# barometer.net
KiCad netlist of a schematic drawn in EAGLE
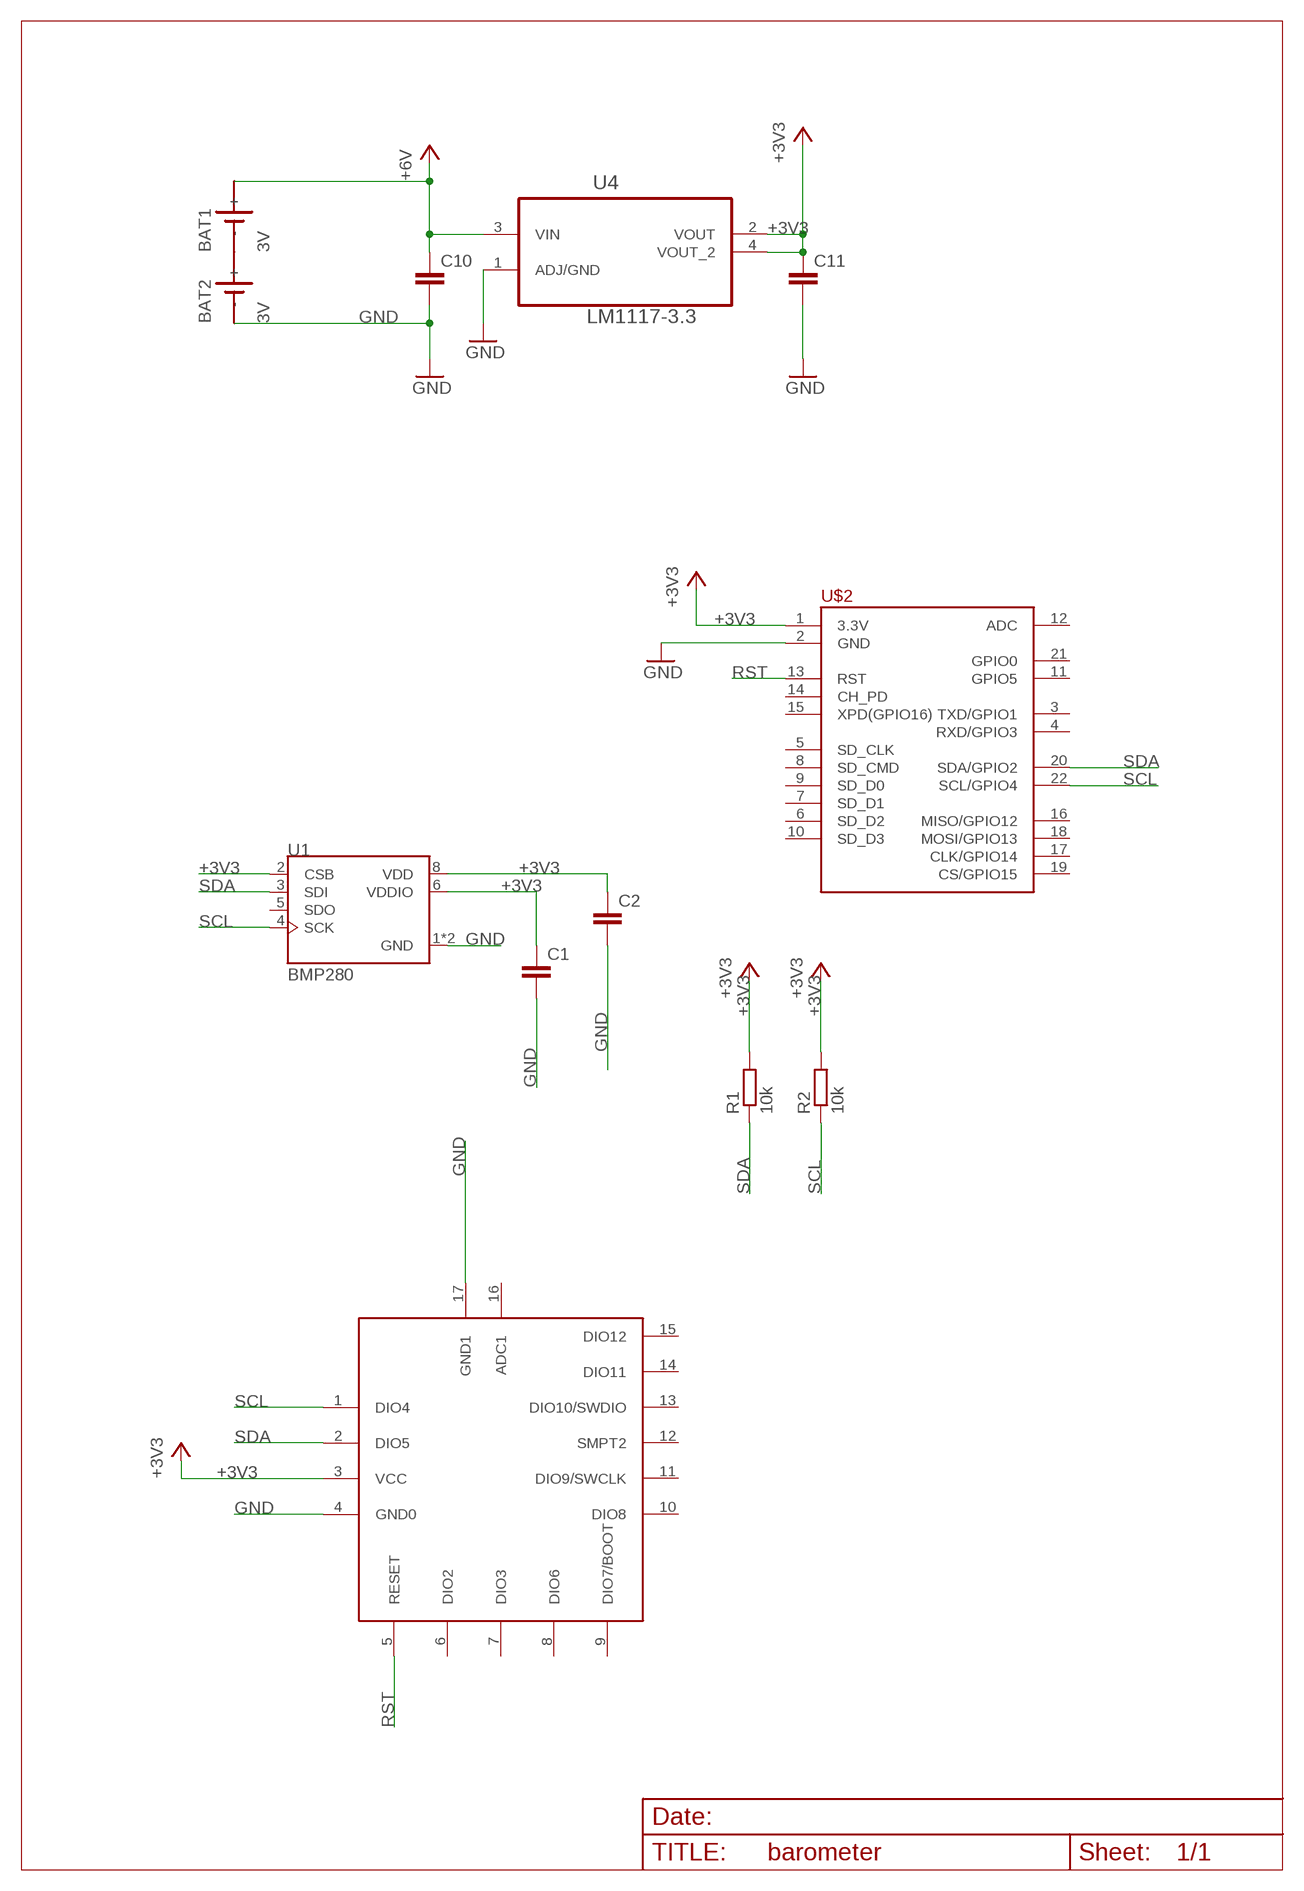
[diagram p0: schematic, sheet 1]

(export (version "E")
  (design (tool "Eeschema 10.0.6"))
  (components
    (comp (ref "BAT1")
      (value "3V")
      (footprint "eagle-import:SN2032")
      (libsource (lib "eagle-import") (part "SN2032"))
    )
    (comp (ref "BAT2")
      (value "3V")
      (footprint "eagle-import:SN2032")
      (libsource (lib "eagle-import") (part "SN2032"))
    )
    (comp (ref "C1")
      (value "47u")
      (footprint "eagle-import:C1206")
      (libsource (lib "eagle-import") (part "C-EUC1206"))
    )
    (comp (ref "C2")
      (value "47u")
      (footprint "eagle-import:C1206")
      (libsource (lib "eagle-import") (part "C-EUC1206"))
    )
    (comp (ref "C10")
      (value "47u")
      (footprint "eagle-import:C1206")
      (libsource (lib "eagle-import") (part "C-EUC1206"))
    )
    (comp (ref "C11")
      (value "10u")
      (footprint "eagle-import:C1206")
      (libsource (lib "eagle-import") (part "C-EUC1206"))
    )
    (comp (ref "R1")
      (value "10k")
      (footprint "eagle-import:R0402")
      (libsource (lib "eagle-import") (part "R-EU_R0402"))
    )
    (comp (ref "R2")
      (value "10k")
      (footprint "eagle-import:R0402")
      (libsource (lib "eagle-import") (part "R-EU_R0402"))
    )
    (comp (ref "U$1")
      (value "BLUENRG-234BLEMODULE")
      (footprint "eagle-import:BLUENRG-234BLEMODULE")
      (libsource (lib "eagle-import") (part "BLUENRG-234BLEMODULE"))
    )
    (comp (ref "U$2")
      (value "OLIMEX_MOD-WIFI-ESP8266-DEV>PINS-OUTSIDE")
      (footprint "eagle-import:OLIMEX_MOD-WIFI-ESP8266-DEV-PINS-OUTSIDE")
      (libsource (lib "eagle-import") (part "OLIMEX_MOD-WIFI-ESP8266-DEV{gt}PINS-OUTSIDE"))
    )
    (comp (ref "U1")
      (value "BMP280")
      (footprint "eagle-import:XDCR_BMP280")
      (fields (field (name "MF") "Bosch"))
      (libsource (lib "eagle-import") (part "BMP280"))
    )
    (comp (ref "U4")
      (value "LM1117-3.3")
      (footprint "eagle-import:SOT230")
      (fields (field (name "MF") "Texas Instruments"))
      (libsource (lib "eagle-import") (part "LM1117-3.3"))
    )
  )
  (nets
    (net (code "1") (name "+3V3") (class "Default")
      (node (ref "C1") (pin "1") (pinfunction "1_1") (pintype "passive"))
      (node (ref "C11") (pin "1") (pinfunction "1_1") (pintype "passive"))
      (node (ref "C2") (pin "1") (pinfunction "1_1") (pintype "passive"))
      (node (ref "R1") (pin "2") (pinfunction "2_2") (pintype "passive"))
      (node (ref "R2") (pin "2") (pinfunction "2_2") (pintype "passive"))
      (node (ref "U$1") (pin "3") (pinfunction "VCC_3") (pintype "bidirectional"))
      (node (ref "U$2") (pin "1") (pinfunction "3.3V_1") (pintype "power_in"))
      (node (ref "U1") (pin "2") (pinfunction "CSB_2") (pintype "input"))
      (node (ref "U1") (pin "6") (pinfunction "VDDIO_6") (pintype "power_in"))
      (node (ref "U1") (pin "8") (pinfunction "VDD_8") (pintype "power_in"))
      (node (ref "U4") (pin "2") (pinfunction "VOUT_2") (pintype "output"))
      (node (ref "U4") (pin "4") (pinfunction "VOUT_2_4") (pintype "output"))
    )
    (net (code "2") (name "+6V") (class "Default")
      (node (ref "BAT1") (pin "+") (pinfunction "+_+") (pintype "passive"))
      (node (ref "C10") (pin "1") (pinfunction "1_1") (pintype "passive"))
      (node (ref "U4") (pin "3") (pinfunction "VIN_3") (pintype "input"))
    )
    (net (code "3") (name "/RST") (class "Default")
      (node (ref "U$1") (pin "5") (pinfunction "RESET_5") (pintype "bidirectional"))
      (node (ref "U$2") (pin "13") (pinfunction "RST_13") (pintype "input"))
    )
    (net (code "4") (name "/SCL") (class "Default")
      (node (ref "R2") (pin "1") (pinfunction "1_1") (pintype "passive"))
      (node (ref "U$1") (pin "1") (pinfunction "DIO4_1") (pintype "bidirectional"))
      (node (ref "U$2") (pin "22") (pinfunction "SCL/GPIO4_22") (pintype "bidirectional"))
      (node (ref "U1") (pin "4") (pinfunction "SCK_4") (pintype "input"))
    )
    (net (code "5") (name "/SDA") (class "Default")
      (node (ref "R1") (pin "1") (pinfunction "1_1") (pintype "passive"))
      (node (ref "U$1") (pin "2") (pinfunction "DIO5_2") (pintype "bidirectional"))
      (node (ref "U$2") (pin "20") (pinfunction "SDA/GPIO2_20") (pintype "bidirectional"))
      (node (ref "U1") (pin "3") (pinfunction "SDI_3") (pintype "bidirectional"))
    )
    (net (code "6") (name "GND") (class "Default")
      (node (ref "BAT2") (pin "-") (pinfunction "-_-") (pintype "passive"))
      (node (ref "C1") (pin "2") (pinfunction "2_2") (pintype "passive"))
      (node (ref "C10") (pin "2") (pinfunction "2_2") (pintype "passive"))
      (node (ref "C11") (pin "2") (pinfunction "2_2") (pintype "passive"))
      (node (ref "C2") (pin "2") (pinfunction "2_2") (pintype "passive"))
      (node (ref "U$1") (pin "17") (pinfunction "GND1_17") (pintype "bidirectional"))
      (node (ref "U$1") (pin "4") (pinfunction "GND0_4") (pintype "bidirectional"))
      (node (ref "U$2") (pin "2") (pinfunction "GND_2") (pintype "power_in"))
      (node (ref "U1") (pin "1") (pinfunction "GND_1") (pintype "power_in"))
      (node (ref "U1") (pin "7") (pinfunction "GND_7") (pintype "power_in"))
      (node (ref "U4") (pin "1") (pinfunction "ADJ/GND_1") (pintype "passive"))
    )
    (net (code "7") (name "Net-(BAT1-Pad-)") (class "Default")
      (node (ref "BAT1") (pin "-") (pinfunction "-_-") (pintype "passive"))
      (node (ref "BAT2") (pin "+") (pinfunction "+_+") (pintype "passive"))
    )
    (net (code "8") (name "unconnected-(U$1-ADC1-Pad16)") (class "Default")
      (node (ref "U$1") (pin "16") (pinfunction "ADC1_16") (pintype "bidirectional"))
    )
    (net (code "9") (name "unconnected-(U$1-DIO2-Pad6)") (class "Default")
      (node (ref "U$1") (pin "6") (pinfunction "DIO2_6") (pintype "bidirectional"))
    )
    (net (code "10") (name "unconnected-(U$1-DIO3-Pad7)") (class "Default")
      (node (ref "U$1") (pin "7") (pinfunction "DIO3_7") (pintype "bidirectional"))
    )
    (net (code "11") (name "unconnected-(U$1-DIO6-Pad8)") (class "Default")
      (node (ref "U$1") (pin "8") (pinfunction "DIO6_8") (pintype "bidirectional"))
    )
    (net (code "12") (name "unconnected-(U$1-DIO7{slash}BOOT-Pad9)") (class "Default")
      (node (ref "U$1") (pin "9") (pinfunction "DIO7/BOOT_9") (pintype "bidirectional"))
    )
    (net (code "13") (name "unconnected-(U$1-DIO8-Pad10)") (class "Default")
      (node (ref "U$1") (pin "10") (pinfunction "DIO8_10") (pintype "bidirectional"))
    )
    (net (code "14") (name "unconnected-(U$1-DIO9{slash}SWCLK-Pad11)") (class "Default")
      (node (ref "U$1") (pin "11") (pinfunction "DIO9/SWCLK_11") (pintype "bidirectional"))
    )
    (net (code "15") (name "unconnected-(U$1-DIO10{slash}SWDIO-Pad13)") (class "Default")
      (node (ref "U$1") (pin "13") (pinfunction "DIO10/SWDIO_13") (pintype "bidirectional"))
    )
    (net (code "16") (name "unconnected-(U$1-DIO11-Pad14)") (class "Default")
      (node (ref "U$1") (pin "14") (pinfunction "DIO11_14") (pintype "bidirectional"))
    )
    (net (code "17") (name "unconnected-(U$1-DIO12-Pad15)") (class "Default")
      (node (ref "U$1") (pin "15") (pinfunction "DIO12_15") (pintype "bidirectional"))
    )
    (net (code "18") (name "unconnected-(U$1-SMPT2-Pad12)") (class "Default")
      (node (ref "U$1") (pin "12") (pinfunction "SMPT2_12") (pintype "bidirectional"))
    )
    (net (code "19") (name "unconnected-(U$2-ADC-Pad12)") (class "Default")
      (node (ref "U$2") (pin "12") (pinfunction "ADC_12") (pintype "bidirectional"))
    )
    (net (code "20") (name "unconnected-(U$2-CH_PD-Pad14)") (class "Default")
      (node (ref "U$2") (pin "14") (pinfunction "CH_PD_14") (pintype "input"))
    )
    (net (code "21") (name "unconnected-(U$2-CLK{slash}GPIO14-Pad17)") (class "Default")
      (node (ref "U$2") (pin "17") (pinfunction "CLK/GPIO14_17") (pintype "bidirectional"))
    )
    (net (code "22") (name "unconnected-(U$2-CS{slash}GPIO15-Pad19)") (class "Default")
      (node (ref "U$2") (pin "19") (pinfunction "CS/GPIO15_19") (pintype "bidirectional"))
    )
    (net (code "23") (name "unconnected-(U$2-GPIO0-Pad21)") (class "Default")
      (node (ref "U$2") (pin "21") (pinfunction "GPIO0_21") (pintype "bidirectional"))
    )
    (net (code "24") (name "unconnected-(U$2-GPIO5-Pad11)") (class "Default")
      (node (ref "U$2") (pin "11") (pinfunction "GPIO5_11") (pintype "bidirectional"))
    )
    (net (code "25") (name "unconnected-(U$2-MISO{slash}GPIO12-Pad16)") (class "Default")
      (node (ref "U$2") (pin "16") (pinfunction "MISO/GPIO12_16") (pintype "bidirectional"))
    )
    (net (code "26") (name "unconnected-(U$2-MOSI{slash}GPIO13-Pad18)") (class "Default")
      (node (ref "U$2") (pin "18") (pinfunction "MOSI/GPIO13_18") (pintype "bidirectional"))
    )
    (net (code "27") (name "unconnected-(U$2-RXD{slash}GPIO3-Pad4)") (class "Default")
      (node (ref "U$2") (pin "4") (pinfunction "RXD/GPIO3_4") (pintype "bidirectional"))
    )
    (net (code "28") (name "unconnected-(U$2-SD_CLK-Pad5)") (class "Default")
      (node (ref "U$2") (pin "5") (pinfunction "SD_CLK_5") (pintype "bidirectional"))
    )
    (net (code "29") (name "unconnected-(U$2-SD_CMD-Pad8)") (class "Default")
      (node (ref "U$2") (pin "8") (pinfunction "SD_CMD_8") (pintype "bidirectional"))
    )
    (net (code "30") (name "unconnected-(U$2-SD_D0-Pad9)") (class "Default")
      (node (ref "U$2") (pin "9") (pinfunction "SD_D0_9") (pintype "bidirectional"))
    )
    (net (code "31") (name "unconnected-(U$2-SD_D1-Pad7)") (class "Default")
      (node (ref "U$2") (pin "7") (pinfunction "SD_D1_7") (pintype "bidirectional"))
    )
    (net (code "32") (name "unconnected-(U$2-SD_D2-Pad6)") (class "Default")
      (node (ref "U$2") (pin "6") (pinfunction "SD_D2_6") (pintype "bidirectional"))
    )
    (net (code "33") (name "unconnected-(U$2-SD_D3-Pad10)") (class "Default")
      (node (ref "U$2") (pin "10") (pinfunction "SD_D3_10") (pintype "bidirectional"))
    )
    (net (code "34") (name "unconnected-(U$2-TXD{slash}GPIO1-Pad3)") (class "Default")
      (node (ref "U$2") (pin "3") (pinfunction "TXD/GPIO1_3") (pintype "bidirectional"))
    )
    (net (code "35") (name "unconnected-(U$2-XPD(GPIO16)-Pad15)") (class "Default")
      (node (ref "U$2") (pin "15") (pinfunction "XPD(GPIO16)_15") (pintype "bidirectional"))
    )
    (net (code "36") (name "unconnected-(U1-SDO-Pad5)") (class "Default")
      (node (ref "U1") (pin "5") (pinfunction "SDO_5") (pintype "bidirectional"))
    )
  )
)
